# ADC_Input_CH.net
KiCad netlist of a schematic drawn in Altium Designer
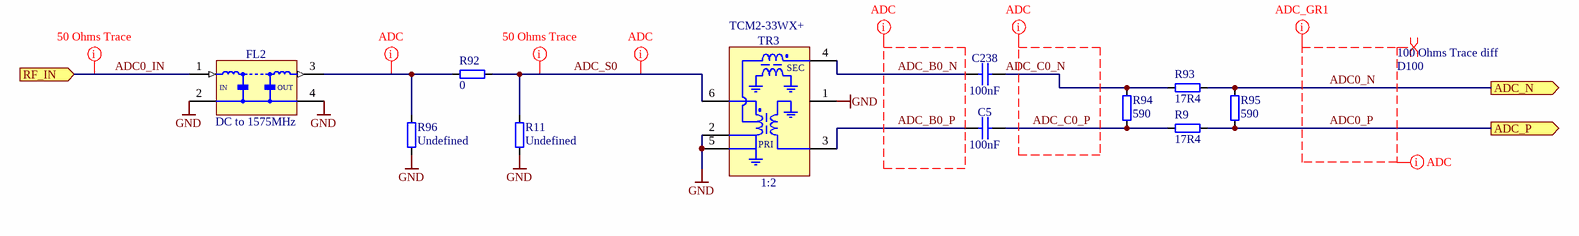
[diagram p0: ADC_Input_CH.SchDoc]

(export (version "E")
  (design (tool "Eeschema 10.0.6"))
  (components
    (comp (ref "C5")
      (value "100nF")
      (footprint "CAPC0603X33N")
      (description "Non-polarised capacitor")
      (fields
        (field (name "PART NUMBER") "CC0201_100NF_6.3V_10%_X5R")
        (field (name "VOLTAGE") "6.3V")
        (field (name "AUTHOR") "CERN DEM JLC")
      )
      (libsource (lib "Capacitors") (part "Capacitor - non polarized"))
    )
    (comp (ref "C238")
      (value "100nF")
      (footprint "CAPC0603X33N")
      (description "Non-polarised capacitor")
      (fields
        (field (name "PART NUMBER") "CC0201_100NF_6.3V_10%_X5R")
        (field (name "VOLTAGE") "6.3V")
        (field (name "AUTHOR") "CERN DEM JLC")
      )
      (libsource (lib "Capacitors") (part "Capacitor - non polarized"))
    )
    (comp (ref "FL2")
      (value "DC to 1575MHz")
      (footprint "FIL_MINI-CIRCUITS_FV1206")
      (description "50 Ohm Low Pass Filter")
      (fields
        (field (name "PART NUMBER") "FIL_MINI-CIRCUITS_LFCN-1575+")
        (field (name "MANUFACTURER") "MINI-CIRCUITS")
        (field (name "AUTHOR") "CERN DEM JLC")
      )
      (libsource (lib "Inductors & Transformers") (part "FIL_MINI-CIRCUITS_LFCN"))
    )
    (comp (ref "R9")
      (value "17R4")
      (footprint "RESC1005X40N")
      (description "Resistor - 1%")
      (fields
        (field (name "TOLERANCE") "±1%")
        (field (name "VOLTAGE") "50V")
        (field (name "AUTHOR") "CERN DEM BC")
      )
      (libsource (lib "Resistors") (part "Resistor - 1%"))
    )
    (comp (ref "R11")
      (value "Undefined")
      (footprint "RESC1005X40N")
      (description "Resistor")
      (fields (field (name "PART NUMBER") "R0402_NO-VALUE") (field (name "AUTHOR") "CERN DEM JLC"))
      (libsource (lib "Resistors") (part "Resistor"))
    )
    (comp (ref "R92")
      (value "0")
      (footprint "RESC1005X40N")
      (description "Resistor")
      (fields
        (field (name "PART NUMBER") "R0402_0R_JUMPER")
        (field (name "MANUFACTURER") "GENERIC")
        (field (name "AUTHOR") "CERN DEM JLC")
      )
      (libsource (lib "Resistors") (part "Resistor"))
    )
    (comp (ref "R93")
      (value "17R4")
      (footprint "RESC1005X40N")
      (description "Resistor - 1%")
      (fields
        (field (name "TOLERANCE") "±1%")
        (field (name "VOLTAGE") "50V")
        (field (name "AUTHOR") "CERN DEM BC")
      )
      (libsource (lib "Resistors") (part "Resistor - 1%"))
    )
    (comp (ref "R94")
      (value "590")
      (footprint "RESC1005X40N")
      (description "Resistor - 1%")
      (fields
        (field (name "TOLERANCE") "±1%")
        (field (name "VOLTAGE") "50V")
        (field (name "AUTHOR") "CERN DEM BC")
      )
      (libsource (lib "Resistors") (part "Resistor - 1%"))
    )
    (comp (ref "R95")
      (value "590")
      (footprint "RESC1005X40N")
      (description "Resistor - 1%")
      (fields
        (field (name "TOLERANCE") "±1%")
        (field (name "VOLTAGE") "50V")
        (field (name "AUTHOR") "CERN DEM BC")
      )
      (libsource (lib "Resistors") (part "Resistor - 1%"))
    )
    (comp (ref "R96")
      (value "Undefined")
      (footprint "RESC1005X40N")
      (description "Resistor")
      (fields (field (name "PART NUMBER") "R0402_NO-VALUE") (field (name "AUTHOR") "CERN DEM JLC"))
      (libsource (lib "Resistors") (part "Resistor"))
    )
    (comp (ref "TR3")
      (value "1:2")
      (footprint "XFMR_MINI-CIRCUITS_DB1627")
      (description "50 OHMS 10 to 3000 MHz RF Transformer")
      (fields
        (field (name "PART NUMBER") "XFMR_MINI-CIRCUITS_TCM2-33WX+")
        (field (name "POWER") "0.4W")
        (field (name "MANUFACTURER PART NUMBER") "TCM2-33WX+")
        (field (name "AUTHOR") "CERN DEM MR")
      )
      (libsource (lib "Inductors & Transformers") (part "XFMR_MINI-CIRCUITS_TCM2-33WX+"))
    )
  )
  (nets
    (net (code "1") (name "/ADC0_IN") (class "Default")
      (node (ref "FL2") (pin "1") (pinfunction "RFIN_1") (pintype "input"))
    )
    (net (code "2") (name "/ADC0_N") (class "Default")
      (node (ref "R93") (pin "2") (pinfunction "2_2") (pintype "passive"))
      (node (ref "R95") (pin "1") (pinfunction "1_1") (pintype "passive"))
    )
    (net (code "3") (name "/ADC0_P") (class "Default")
      (node (ref "R9") (pin "2") (pinfunction "2_2") (pintype "passive"))
      (node (ref "R95") (pin "2") (pinfunction "2_2") (pintype "passive"))
    )
    (net (code "4") (name "/ADC_B0_N") (class "Default")
      (node (ref "C238") (pin "1") (pinfunction "1_1") (pintype "passive"))
      (node (ref "TR3") (pin "4") (pinfunction "SD_4") (pintype "passive"))
    )
    (net (code "5") (name "/ADC_B0_P") (class "Default")
      (node (ref "C5") (pin "1") (pinfunction "1_1") (pintype "passive"))
      (node (ref "TR3") (pin "3") (pinfunction "S_3") (pintype "passive"))
    )
    (net (code "6") (name "/ADC_C0_N") (class "Default")
      (node (ref "C238") (pin "2") (pinfunction "2_2") (pintype "passive"))
      (node (ref "R93") (pin "1") (pinfunction "1_1") (pintype "passive"))
      (node (ref "R94") (pin "1") (pinfunction "1_1") (pintype "passive"))
    )
    (net (code "7") (name "/ADC_C0_P") (class "Default")
      (node (ref "C5") (pin "2") (pinfunction "2_2") (pintype "passive"))
      (node (ref "R9") (pin "1") (pinfunction "1_1") (pintype "passive"))
      (node (ref "R94") (pin "2") (pinfunction "2_2") (pintype "passive"))
    )
    (net (code "8") (name "/ADC_S0") (class "Default")
      (node (ref "R11") (pin "1") (pinfunction "1_1") (pintype "passive"))
      (node (ref "R92") (pin "2") (pinfunction "2_2") (pintype "passive"))
      (node (ref "TR3") (pin "6") (pinfunction "P1_6") (pintype "passive"))
    )
    (net (code "9") (name "GND") (class "Default")
      (node (ref "FL2") (pin "2") (pinfunction "GND_2") (pintype "power_in"))
      (node (ref "FL2") (pin "4") (pinfunction "GND_4") (pintype "power_in"))
      (node (ref "R11") (pin "2") (pinfunction "2_2") (pintype "passive"))
      (node (ref "R96") (pin "2") (pinfunction "2_2") (pintype "passive"))
      (node (ref "TR3") (pin "1") (pinfunction "NC_1") (pintype "passive"))
      (node (ref "TR3") (pin "2") (pinfunction "P_2") (pintype "passive"))
      (node (ref "TR3") (pin "5") (pinfunction "GND_5") (pintype "power_in"))
    )
    (net (code "10") (name "Net-(FL2-RFOUT)") (class "Default")
      (node (ref "FL2") (pin "3") (pinfunction "RFOUT_3") (pintype "output"))
      (node (ref "R92") (pin "1") (pinfunction "1_1") (pintype "passive"))
      (node (ref "R96") (pin "1") (pinfunction "1_1") (pintype "passive"))
    )
  )
)
